# deska.net
KiCad netlist of a schematic drawn in EAGLE
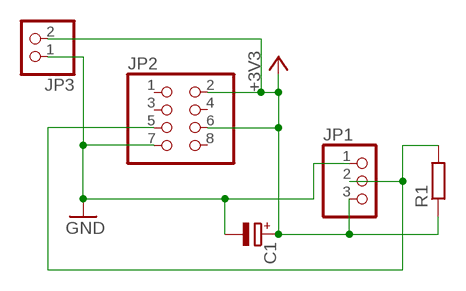
[diagram p0: schematic, sheet 1]

(export (version "E")
  (design (tool "Eeschema 10.0.6"))
  (components
    (comp (ref "C1")
      (value "CPOL-EUE3.5-8")
      (footprint "eagle-import:E3,5-8")
      (libsource (lib "eagle-import") (part "CPOL-EUE3.5-8"))
    )
    (comp (ref "JP1")
      (value "PINHD-1X3")
      (footprint "eagle-import:1X03")
      (libsource (lib "eagle-import") (part "PINHD-1X3"))
    )
    (comp (ref "JP2")
      (value "PINHD-2X4")
      (footprint "eagle-import:2X04")
      (libsource (lib "eagle-import") (part "PINHD-2X4"))
    )
    (comp (ref "JP3")
      (value "PINHD-1X2")
      (footprint "eagle-import:1X02")
      (libsource (lib "eagle-import") (part "PINHD-1X2"))
    )
    (comp (ref "R1")
      (value "R-EU_0204/7")
      (footprint "eagle-import:0204_7")
      (libsource (lib "eagle-import") (part "R-EU_0204/7"))
    )
  )
  (nets
    (net (code "1") (name "+3V3") (class "Default")
      (node (ref "C1") (pin "+") (pinfunction "+_+") (pintype "passive"))
      (node (ref "JP1") (pin "3") (pinfunction "3_3") (pintype "passive"))
      (node (ref "JP2") (pin "2") (pinfunction "2_2") (pintype "passive"))
      (node (ref "JP2") (pin "6") (pinfunction "6_6") (pintype "passive"))
      (node (ref "JP3") (pin "2") (pinfunction "2_2") (pintype "passive"))
      (node (ref "R1") (pin "1") (pinfunction "1_1") (pintype "passive"))
    )
    (net (code "2") (name "GND") (class "Default")
      (node (ref "C1") (pin "-") (pinfunction "-_-") (pintype "passive"))
      (node (ref "JP1") (pin "1") (pinfunction "1_1") (pintype "passive"))
      (node (ref "JP2") (pin "7") (pinfunction "7_7") (pintype "passive"))
      (node (ref "JP3") (pin "1") (pinfunction "1_1") (pintype "passive"))
    )
    (net (code "3") (name "Net-(JP1-Pad2)") (class "Default")
      (node (ref "JP1") (pin "2") (pinfunction "2_2") (pintype "passive"))
      (node (ref "JP2") (pin "5") (pinfunction "5_5") (pintype "passive"))
      (node (ref "R1") (pin "2") (pinfunction "2_2") (pintype "passive"))
    )
    (net (code "4") (name "unconnected-(JP2-Pad1)") (class "Default")
      (node (ref "JP2") (pin "1") (pinfunction "1_1") (pintype "passive"))
    )
    (net (code "5") (name "unconnected-(JP2-Pad3)") (class "Default")
      (node (ref "JP2") (pin "3") (pinfunction "3_3") (pintype "passive"))
    )
    (net (code "6") (name "unconnected-(JP2-Pad4)") (class "Default")
      (node (ref "JP2") (pin "4") (pinfunction "4_4") (pintype "passive"))
    )
    (net (code "7") (name "unconnected-(JP2-Pad8)") (class "Default")
      (node (ref "JP2") (pin "8") (pinfunction "8_8") (pintype "passive"))
    )
  )
)
